# PCM5102a_FG.net
KiCad netlist of a schematic drawn in EAGLE
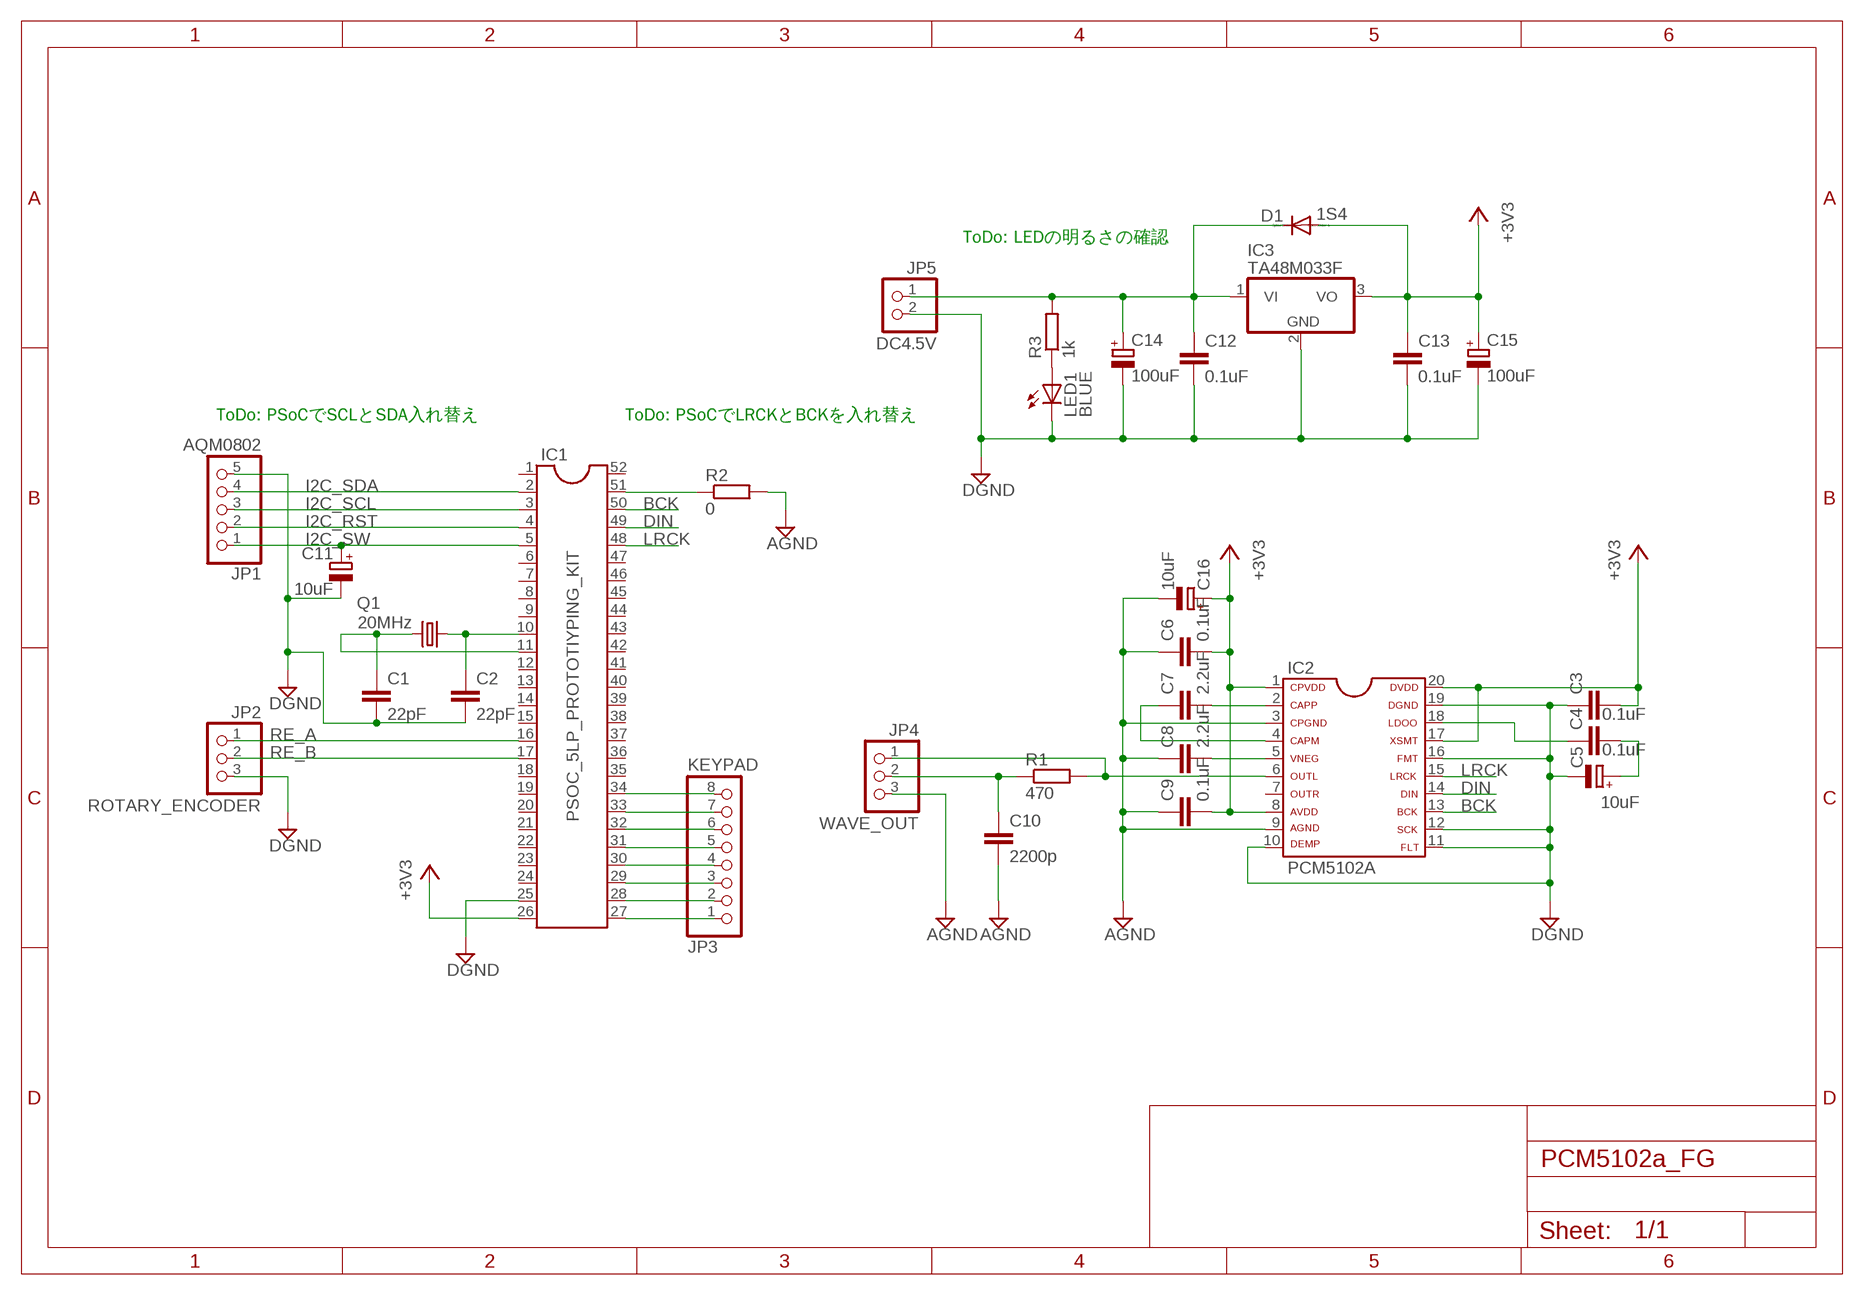
[diagram p0: schematic, sheet 1]

(export (version "E")
  (design (tool "Eeschema 10.0.6"))
  (components
    (comp (ref "C1")
      (value "22pF")
      (footprint "eagle-import:C025-024X044")
      (libsource (lib "eagle-import") (part "C-EU025-024X044"))
    )
    (comp (ref "C2")
      (value "22pF")
      (footprint "eagle-import:C025-024X044")
      (libsource (lib "eagle-import") (part "C-EU025-024X044"))
    )
    (comp (ref "C3")
      (value "0.1uF")
      (footprint "eagle-import:C025-024X044")
      (libsource (lib "eagle-import") (part "C-EU025-024X044"))
    )
    (comp (ref "C4")
      (value "0.1uF")
      (footprint "eagle-import:C025-024X044")
      (libsource (lib "eagle-import") (part "C-EU025-024X044"))
    )
    (comp (ref "C5")
      (value "10uF")
      (footprint "eagle-import:E2,5-5")
      (libsource (lib "eagle-import") (part "CPOL-EUE2.5-5"))
    )
    (comp (ref "C6")
      (value "0.1uF")
      (footprint "eagle-import:C025-024X044")
      (libsource (lib "eagle-import") (part "C-EU025-024X044"))
    )
    (comp (ref "C7")
      (value "2.2uF")
      (footprint "eagle-import:C075-063X106")
      (libsource (lib "eagle-import") (part "C-EU075-063X106"))
    )
    (comp (ref "C8")
      (value "2.2uF")
      (footprint "eagle-import:C075-063X106")
      (libsource (lib "eagle-import") (part "C-EU075-063X106"))
    )
    (comp (ref "C9")
      (value "0.1uF")
      (footprint "eagle-import:C025-024X044")
      (libsource (lib "eagle-import") (part "C-EU025-024X044"))
    )
    (comp (ref "C10")
      (value "2200p")
      (footprint "eagle-import:C050-035X075")
      (libsource (lib "eagle-import") (part "C-EU050-035X075"))
    )
    (comp (ref "C11")
      (value "10uF")
      (footprint "eagle-import:E2,5-5")
      (libsource (lib "eagle-import") (part "CPOL-EUE2.5-5"))
    )
    (comp (ref "C12")
      (value "0.1uF")
      (footprint "eagle-import:C025-024X044")
      (libsource (lib "eagle-import") (part "C-EU025-024X044"))
    )
    (comp (ref "C13")
      (value "0.1uF")
      (footprint "eagle-import:C025-024X044")
      (libsource (lib "eagle-import") (part "C-EU025-024X044"))
    )
    (comp (ref "C14")
      (value "100uF")
      (footprint "eagle-import:E2,5-7")
      (libsource (lib "eagle-import") (part "CPOL-EUE2.5-7"))
    )
    (comp (ref "C15")
      (value "100uF")
      (footprint "eagle-import:E2,5-7")
      (libsource (lib "eagle-import") (part "CPOL-EUE2.5-7"))
    )
    (comp (ref "C16")
      (value "10uF")
      (footprint "eagle-import:E2,5-5")
      (libsource (lib "eagle-import") (part "CPOL-EUE2.5-5"))
    )
    (comp (ref "D1")
      (value "1S4")
      (footprint "eagle-import:DO41-10")
      (libsource (lib "eagle-import") (part "1N4004"))
    )
    (comp (ref "IC1")
      (value "PSOC_5LP_PROTOTIYPING_KIT")
      (footprint "eagle-import:DIL52-8")
      (libsource (lib "eagle-import") (part "PSOC_5LP_PROTOTIYPING_KIT"))
    )
    (comp (ref "IC2")
      (value "PCM5102A")
      (footprint "eagle-import:DIL20-6")
      (libsource (lib "eagle-import") (part "PCM5102A"))
    )
    (comp (ref "IC3")
      (value "TA48M033F")
      (footprint "eagle-import:TO220V")
      (libsource (lib "eagle-import") (part "78TV05"))
    )
    (comp (ref "JP1")
      (value "AQM0802")
      (footprint "eagle-import:1X05")
      (libsource (lib "eagle-import") (part "PINHD-1X5"))
    )
    (comp (ref "JP2")
      (value "ROTARY_ENCODER")
      (footprint "eagle-import:1X03")
      (libsource (lib "eagle-import") (part "PINHD-1X3"))
    )
    (comp (ref "JP3")
      (value "KEYPAD")
      (footprint "eagle-import:1X08")
      (libsource (lib "eagle-import") (part "PINHD-1X8"))
    )
    (comp (ref "JP4")
      (value "WAVE_OUT")
      (footprint "eagle-import:1X03")
      (libsource (lib "eagle-import") (part "PINHD-1X3"))
    )
    (comp (ref "JP5")
      (value "DC4.5V")
      (footprint "eagle-import:1X02")
      (libsource (lib "eagle-import") (part "PINHD-1X2"))
    )
    (comp (ref "LED1")
      (value "BLUE")
      (footprint "eagle-import:LED3MM")
      (libsource (lib "eagle-import") (part "LED3MM"))
    )
    (comp (ref "Q1")
      (value "20MHz")
      (footprint "eagle-import:HC49_S")
      (libsource (lib "eagle-import") (part "CRYSTALHC49S"))
    )
    (comp (ref "R1")
      (value "470")
      (footprint "eagle-import:0207_7")
      (libsource (lib "eagle-import") (part "R-EU_0207/7"))
    )
    (comp (ref "R2")
      (value "0")
      (footprint "eagle-import:0207_7")
      (libsource (lib "eagle-import") (part "resistor_R-EU_0207/7"))
    )
    (comp (ref "R3")
      (value "1k")
      (footprint "eagle-import:0207_7")
      (libsource (lib "eagle-import") (part "resistor_R-EU_0207/7"))
    )
  )
  (nets
    (net (code "1") (name "+3V3") (class "Default")
      (node (ref "C13") (pin "1") (pinfunction "1_1") (pintype "passive"))
      (node (ref "C15") (pin "+") (pinfunction "+_+") (pintype "passive"))
      (node (ref "C16") (pin "+") (pinfunction "+_+") (pintype "passive"))
      (node (ref "C3") (pin "2") (pinfunction "2_2") (pintype "passive"))
      (node (ref "C6") (pin "2") (pinfunction "2_2") (pintype "passive"))
      (node (ref "C9") (pin "2") (pinfunction "2_2") (pintype "passive"))
      (node (ref "D1") (pin "A") (pinfunction "A_A") (pintype "passive"))
      (node (ref "IC1") (pin "26") (pinfunction "26_26") (pintype "passive"))
      (node (ref "IC2") (pin "1") (pinfunction "1_1") (pintype "passive"))
      (node (ref "IC2") (pin "17") (pinfunction "17_17") (pintype "passive"))
      (node (ref "IC2") (pin "20") (pinfunction "20_20") (pintype "passive"))
      (node (ref "IC2") (pin "8") (pinfunction "8_8") (pintype "passive"))
      (node (ref "IC3") (pin "3") (pinfunction "VO_3") (pintype "passive"))
    )
    (net (code "2") (name "/BCK") (class "Default")
      (node (ref "IC1") (pin "50") (pinfunction "50_50") (pintype "passive"))
      (node (ref "IC2") (pin "13") (pinfunction "13_13") (pintype "passive"))
    )
    (net (code "3") (name "/DIN") (class "Default")
      (node (ref "IC1") (pin "49") (pinfunction "49_49") (pintype "passive"))
      (node (ref "IC2") (pin "14") (pinfunction "14_14") (pintype "passive"))
    )
    (net (code "4") (name "/I2C_RST") (class "Default")
      (node (ref "IC1") (pin "4") (pinfunction "4_4") (pintype "passive"))
      (node (ref "JP1") (pin "2") (pinfunction "2_2") (pintype "passive"))
    )
    (net (code "5") (name "/I2C_SCL") (class "Default")
      (node (ref "IC1") (pin "3") (pinfunction "3_3") (pintype "passive"))
      (node (ref "JP1") (pin "3") (pinfunction "3_3") (pintype "passive"))
    )
    (net (code "6") (name "/I2C_SDA") (class "Default")
      (node (ref "IC1") (pin "2") (pinfunction "2_2") (pintype "passive"))
      (node (ref "JP1") (pin "4") (pinfunction "4_4") (pintype "passive"))
    )
    (net (code "7") (name "/I2C_SW") (class "Default")
      (node (ref "C11") (pin "+") (pinfunction "+_+") (pintype "passive"))
      (node (ref "IC1") (pin "5") (pinfunction "5_5") (pintype "passive"))
      (node (ref "JP1") (pin "1") (pinfunction "1_1") (pintype "passive"))
    )
    (net (code "8") (name "/LRCK") (class "Default")
      (node (ref "IC1") (pin "48") (pinfunction "48_48") (pintype "passive"))
      (node (ref "IC2") (pin "15") (pinfunction "15_15") (pintype "passive"))
    )
    (net (code "9") (name "/RE_A") (class "Default")
      (node (ref "IC1") (pin "16") (pinfunction "16_16") (pintype "passive"))
      (node (ref "JP2") (pin "1") (pinfunction "1_1") (pintype "passive"))
    )
    (net (code "10") (name "/RE_B") (class "Default")
      (node (ref "IC1") (pin "17") (pinfunction "17_17") (pintype "passive"))
      (node (ref "JP2") (pin "2") (pinfunction "2_2") (pintype "passive"))
    )
    (net (code "11") (name "AGND") (class "Default")
      (node (ref "C10") (pin "2") (pinfunction "2_2") (pintype "passive"))
      (node (ref "C16") (pin "-") (pinfunction "-_-") (pintype "passive"))
      (node (ref "C6") (pin "1") (pinfunction "1_1") (pintype "passive"))
      (node (ref "C8") (pin "1") (pinfunction "1_1") (pintype "passive"))
      (node (ref "C9") (pin "1") (pinfunction "1_1") (pintype "passive"))
      (node (ref "IC2") (pin "3") (pinfunction "3_3") (pintype "passive"))
      (node (ref "IC2") (pin "9") (pinfunction "9_9") (pintype "passive"))
      (node (ref "JP4") (pin "3") (pinfunction "3_3") (pintype "passive"))
      (node (ref "R2") (pin "2") (pinfunction "2_2") (pintype "passive"))
    )
    (net (code "12") (name "DGND") (class "Default")
      (node (ref "C1") (pin "2") (pinfunction "2_2") (pintype "passive"))
      (node (ref "C11") (pin "-") (pinfunction "-_-") (pintype "passive"))
      (node (ref "C12") (pin "2") (pinfunction "2_2") (pintype "passive"))
      (node (ref "C13") (pin "2") (pinfunction "2_2") (pintype "passive"))
      (node (ref "C14") (pin "-") (pinfunction "-_-") (pintype "passive"))
      (node (ref "C15") (pin "-") (pinfunction "-_-") (pintype "passive"))
      (node (ref "C2") (pin "2") (pinfunction "2_2") (pintype "passive"))
      (node (ref "C3") (pin "1") (pinfunction "1_1") (pintype "passive"))
      (node (ref "C5") (pin "-") (pinfunction "-_-") (pintype "passive"))
      (node (ref "IC1") (pin "25") (pinfunction "25_25") (pintype "passive"))
      (node (ref "IC2") (pin "10") (pinfunction "10_10") (pintype "passive"))
      (node (ref "IC2") (pin "11") (pinfunction "11_11") (pintype "passive"))
      (node (ref "IC2") (pin "12") (pinfunction "12_12") (pintype "passive"))
      (node (ref "IC2") (pin "16") (pinfunction "16_16") (pintype "passive"))
      (node (ref "IC2") (pin "19") (pinfunction "19_19") (pintype "passive"))
      (node (ref "IC3") (pin "2") (pinfunction "GND_2") (pintype "passive"))
      (node (ref "JP1") (pin "5") (pinfunction "5_5") (pintype "passive"))
      (node (ref "JP2") (pin "3") (pinfunction "3_3") (pintype "passive"))
      (node (ref "JP5") (pin "2") (pinfunction "2_2") (pintype "passive"))
      (node (ref "LED1") (pin "K") (pinfunction "C_K") (pintype "passive"))
    )
    (net (code "13") (name "Net-(C1-Pad1)") (class "Default")
      (node (ref "C1") (pin "1") (pinfunction "1_1") (pintype "passive"))
      (node (ref "IC1") (pin "11") (pinfunction "11_11") (pintype "passive"))
      (node (ref "Q1") (pin "2") (pinfunction "2_2") (pintype "passive"))
    )
    (net (code "14") (name "Net-(C2-Pad1)") (class "Default")
      (node (ref "C2") (pin "1") (pinfunction "1_1") (pintype "passive"))
      (node (ref "IC1") (pin "10") (pinfunction "10_10") (pintype "passive"))
      (node (ref "Q1") (pin "1") (pinfunction "1_1") (pintype "passive"))
    )
    (net (code "15") (name "Net-(C4-Pad1)") (class "Default")
      (node (ref "C4") (pin "1") (pinfunction "1_1") (pintype "passive"))
      (node (ref "IC2") (pin "18") (pinfunction "18_18") (pintype "passive"))
    )
    (net (code "16") (name "Net-(C4-Pad2)") (class "Default")
      (node (ref "C4") (pin "2") (pinfunction "2_2") (pintype "passive"))
      (node (ref "C5") (pin "+") (pinfunction "+_+") (pintype "passive"))
    )
    (net (code "17") (name "Net-(C7-Pad1)") (class "Default")
      (node (ref "C7") (pin "1") (pinfunction "1_1") (pintype "passive"))
      (node (ref "IC2") (pin "4") (pinfunction "4_4") (pintype "passive"))
    )
    (net (code "18") (name "Net-(C7-Pad2)") (class "Default")
      (node (ref "C7") (pin "2") (pinfunction "2_2") (pintype "passive"))
      (node (ref "IC2") (pin "2") (pinfunction "2_2") (pintype "passive"))
    )
    (net (code "19") (name "Net-(C8-Pad2)") (class "Default")
      (node (ref "C8") (pin "2") (pinfunction "2_2") (pintype "passive"))
      (node (ref "IC2") (pin "5") (pinfunction "5_5") (pintype "passive"))
    )
    (net (code "20") (name "Net-(C10-Pad1)") (class "Default")
      (node (ref "C10") (pin "1") (pinfunction "1_1") (pintype "passive"))
      (node (ref "JP4") (pin "2") (pinfunction "2_2") (pintype "passive"))
      (node (ref "R1") (pin "1") (pinfunction "1_1") (pintype "passive"))
    )
    (net (code "21") (name "Net-(IC1-Pad27)") (class "Default")
      (node (ref "IC1") (pin "27") (pinfunction "27_27") (pintype "passive"))
      (node (ref "JP3") (pin "1") (pinfunction "1_1") (pintype "passive"))
    )
    (net (code "22") (name "Net-(IC1-Pad28)") (class "Default")
      (node (ref "IC1") (pin "28") (pinfunction "28_28") (pintype "passive"))
      (node (ref "JP3") (pin "2") (pinfunction "2_2") (pintype "passive"))
    )
    (net (code "23") (name "Net-(IC1-Pad29)") (class "Default")
      (node (ref "IC1") (pin "29") (pinfunction "29_29") (pintype "passive"))
      (node (ref "JP3") (pin "3") (pinfunction "3_3") (pintype "passive"))
    )
    (net (code "24") (name "Net-(IC1-Pad30)") (class "Default")
      (node (ref "IC1") (pin "30") (pinfunction "30_30") (pintype "passive"))
      (node (ref "JP3") (pin "4") (pinfunction "4_4") (pintype "passive"))
    )
    (net (code "25") (name "Net-(IC1-Pad31)") (class "Default")
      (node (ref "IC1") (pin "31") (pinfunction "31_31") (pintype "passive"))
      (node (ref "JP3") (pin "5") (pinfunction "5_5") (pintype "passive"))
    )
    (net (code "26") (name "Net-(IC1-Pad32)") (class "Default")
      (node (ref "IC1") (pin "32") (pinfunction "32_32") (pintype "passive"))
      (node (ref "JP3") (pin "6") (pinfunction "6_6") (pintype "passive"))
    )
    (net (code "27") (name "Net-(IC1-Pad33)") (class "Default")
      (node (ref "IC1") (pin "33") (pinfunction "33_33") (pintype "passive"))
      (node (ref "JP3") (pin "7") (pinfunction "7_7") (pintype "passive"))
    )
    (net (code "28") (name "Net-(IC1-Pad34)") (class "Default")
      (node (ref "IC1") (pin "34") (pinfunction "34_34") (pintype "passive"))
      (node (ref "JP3") (pin "8") (pinfunction "8_8") (pintype "passive"))
    )
    (net (code "29") (name "Net-(IC1-Pad51)") (class "Default")
      (node (ref "IC1") (pin "51") (pinfunction "51_51") (pintype "passive"))
      (node (ref "R2") (pin "1") (pinfunction "1_1") (pintype "passive"))
    )
    (net (code "30") (name "Net-(IC2-Pad6)") (class "Default")
      (node (ref "IC2") (pin "6") (pinfunction "6_6") (pintype "passive"))
      (node (ref "JP4") (pin "1") (pinfunction "1_1") (pintype "passive"))
      (node (ref "R1") (pin "2") (pinfunction "2_2") (pintype "passive"))
    )
    (net (code "31") (name "Net-(IC3-VI)") (class "Default")
      (node (ref "C12") (pin "1") (pinfunction "1_1") (pintype "passive"))
      (node (ref "C14") (pin "+") (pinfunction "+_+") (pintype "passive"))
      (node (ref "D1") (pin "C") (pinfunction "C_C") (pintype "passive"))
      (node (ref "IC3") (pin "1") (pinfunction "VI_1") (pintype "input"))
      (node (ref "JP5") (pin "1") (pinfunction "1_1") (pintype "passive"))
      (node (ref "R3") (pin "2") (pinfunction "2_2") (pintype "passive"))
    )
    (net (code "32") (name "Net-(LED1-PadA)") (class "Default")
      (node (ref "LED1") (pin "A") (pinfunction "A_A") (pintype "passive"))
      (node (ref "R3") (pin "1") (pinfunction "1_1") (pintype "passive"))
    )
    (net (code "33") (name "unconnected-(IC1-Pad1)") (class "Default")
      (node (ref "IC1") (pin "1") (pinfunction "1_1") (pintype "passive"))
    )
    (net (code "34") (name "unconnected-(IC1-Pad6)") (class "Default")
      (node (ref "IC1") (pin "6") (pinfunction "6_6") (pintype "passive"))
    )
    (net (code "35") (name "unconnected-(IC1-Pad7)") (class "Default")
      (node (ref "IC1") (pin "7") (pinfunction "7_7") (pintype "passive"))
    )
    (net (code "36") (name "unconnected-(IC1-Pad8)") (class "Default")
      (node (ref "IC1") (pin "8") (pinfunction "8_8") (pintype "passive"))
    )
    (net (code "37") (name "unconnected-(IC1-Pad9)") (class "Default")
      (node (ref "IC1") (pin "9") (pinfunction "9_9") (pintype "passive"))
    )
    (net (code "38") (name "unconnected-(IC1-Pad12)") (class "Default")
      (node (ref "IC1") (pin "12") (pinfunction "12_12") (pintype "passive"))
    )
    (net (code "39") (name "unconnected-(IC1-Pad13)") (class "Default")
      (node (ref "IC1") (pin "13") (pinfunction "13_13") (pintype "passive"))
    )
    (net (code "40") (name "unconnected-(IC1-Pad14)") (class "Default")
      (node (ref "IC1") (pin "14") (pinfunction "14_14") (pintype "passive"))
    )
    (net (code "41") (name "unconnected-(IC1-Pad15)") (class "Default")
      (node (ref "IC1") (pin "15") (pinfunction "15_15") (pintype "passive"))
    )
    (net (code "42") (name "unconnected-(IC1-Pad18)") (class "Default")
      (node (ref "IC1") (pin "18") (pinfunction "18_18") (pintype "passive"))
    )
    (net (code "43") (name "unconnected-(IC1-Pad19)") (class "Default")
      (node (ref "IC1") (pin "19") (pinfunction "19_19") (pintype "passive"))
    )
    (net (code "44") (name "unconnected-(IC1-Pad20)") (class "Default")
      (node (ref "IC1") (pin "20") (pinfunction "20_20") (pintype "passive"))
    )
    (net (code "45") (name "unconnected-(IC1-Pad21)") (class "Default")
      (node (ref "IC1") (pin "21") (pinfunction "21_21") (pintype "passive"))
    )
    (net (code "46") (name "unconnected-(IC1-Pad22)") (class "Default")
      (node (ref "IC1") (pin "22") (pinfunction "22_22") (pintype "passive"))
    )
    (net (code "47") (name "unconnected-(IC1-Pad23)") (class "Default")
      (node (ref "IC1") (pin "23") (pinfunction "23_23") (pintype "passive"))
    )
    (net (code "48") (name "unconnected-(IC1-Pad24)") (class "Default")
      (node (ref "IC1") (pin "24") (pinfunction "24_24") (pintype "passive"))
    )
    (net (code "49") (name "unconnected-(IC1-Pad35)") (class "Default")
      (node (ref "IC1") (pin "35") (pinfunction "35_35") (pintype "passive"))
    )
    (net (code "50") (name "unconnected-(IC1-Pad36)") (class "Default")
      (node (ref "IC1") (pin "36") (pinfunction "36_36") (pintype "passive"))
    )
    (net (code "51") (name "unconnected-(IC1-Pad37)") (class "Default")
      (node (ref "IC1") (pin "37") (pinfunction "37_37") (pintype "passive"))
    )
    (net (code "52") (name "unconnected-(IC1-Pad38)") (class "Default")
      (node (ref "IC1") (pin "38") (pinfunction "38_38") (pintype "passive"))
    )
    (net (code "53") (name "unconnected-(IC1-Pad39)") (class "Default")
      (node (ref "IC1") (pin "39") (pinfunction "39_39") (pintype "passive"))
    )
    (net (code "54") (name "unconnected-(IC1-Pad40)") (class "Default")
      (node (ref "IC1") (pin "40") (pinfunction "40_40") (pintype "passive"))
    )
    (net (code "55") (name "unconnected-(IC1-Pad41)") (class "Default")
      (node (ref "IC1") (pin "41") (pinfunction "41_41") (pintype "passive"))
    )
    (net (code "56") (name "unconnected-(IC1-Pad42)") (class "Default")
      (node (ref "IC1") (pin "42") (pinfunction "42_42") (pintype "passive"))
    )
    (net (code "57") (name "unconnected-(IC1-Pad43)") (class "Default")
      (node (ref "IC1") (pin "43") (pinfunction "43_43") (pintype "passive"))
    )
    (net (code "58") (name "unconnected-(IC1-Pad44)") (class "Default")
      (node (ref "IC1") (pin "44") (pinfunction "44_44") (pintype "passive"))
    )
    (net (code "59") (name "unconnected-(IC1-Pad45)") (class "Default")
      (node (ref "IC1") (pin "45") (pinfunction "45_45") (pintype "passive"))
    )
    (net (code "60") (name "unconnected-(IC1-Pad46)") (class "Default")
      (node (ref "IC1") (pin "46") (pinfunction "46_46") (pintype "passive"))
    )
    (net (code "61") (name "unconnected-(IC1-Pad47)") (class "Default")
      (node (ref "IC1") (pin "47") (pinfunction "47_47") (pintype "passive"))
    )
    (net (code "62") (name "unconnected-(IC1-Pad52)") (class "Default")
      (node (ref "IC1") (pin "52") (pinfunction "52_52") (pintype "passive"))
    )
    (net (code "63") (name "unconnected-(IC2-Pad7)") (class "Default")
      (node (ref "IC2") (pin "7") (pinfunction "7_7") (pintype "passive"))
    )
  )
)
